# untitled.net
KiCad netlist of a schematic drawn in EAGLE
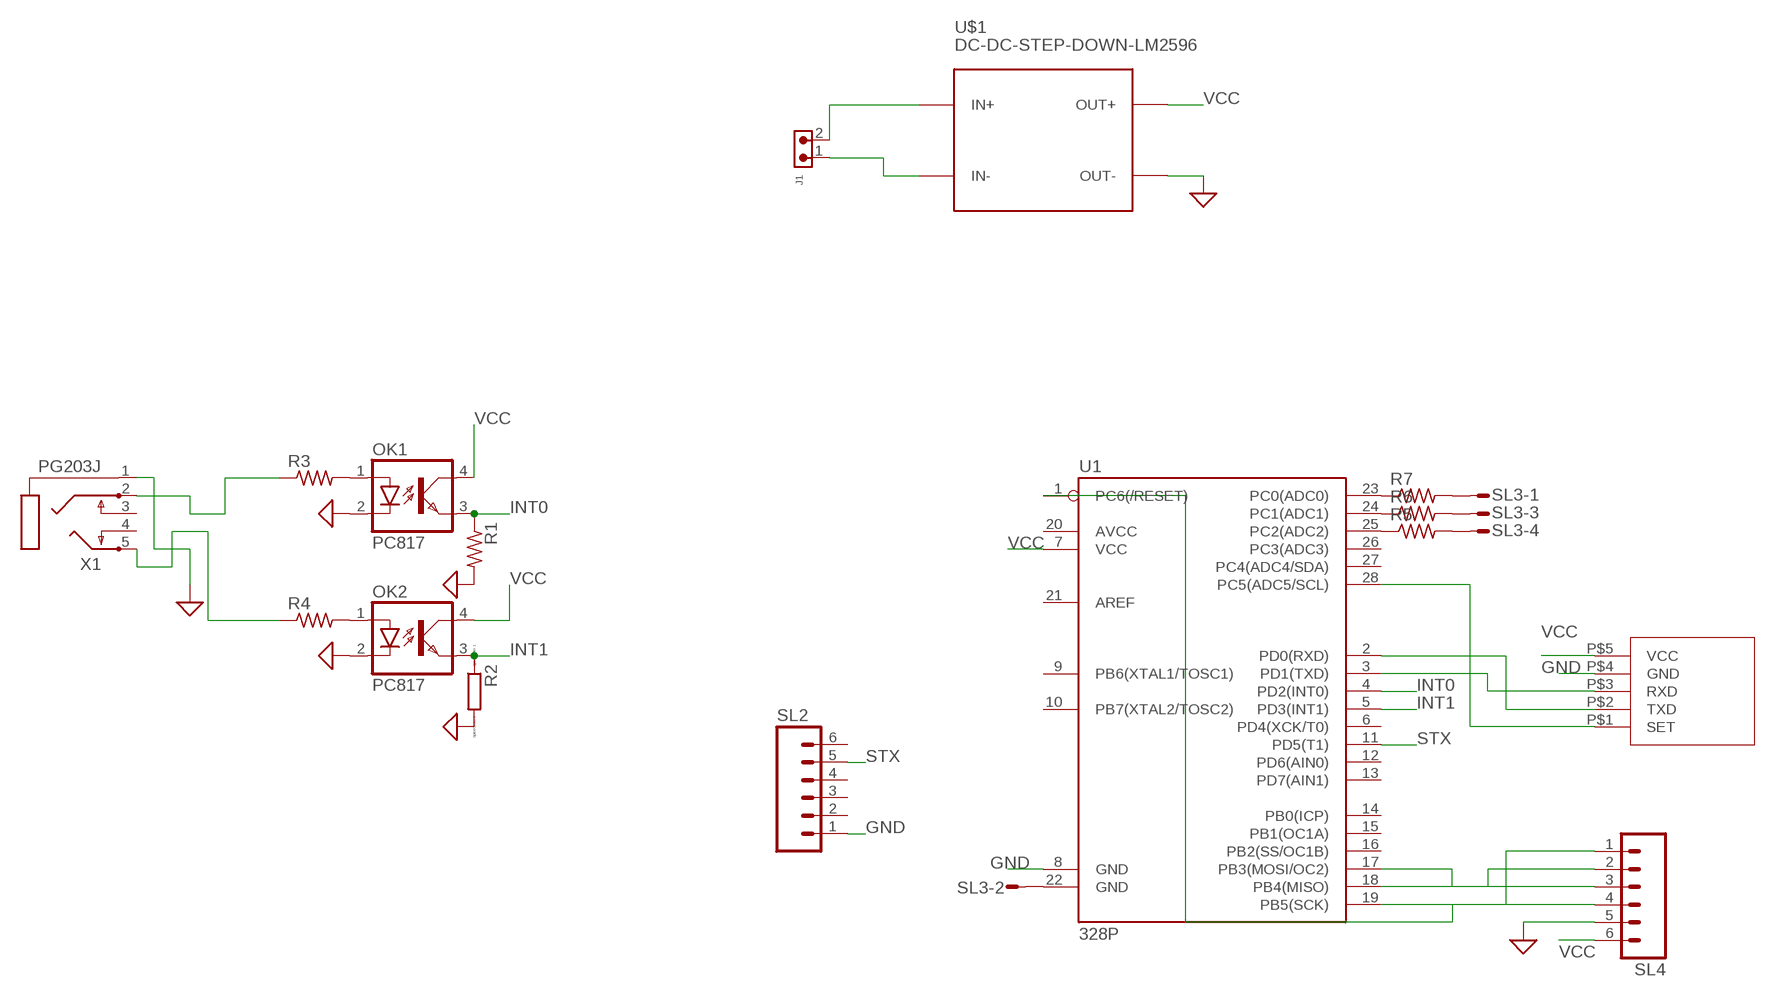
[diagram p0: schematic, sheet 1]

(export (version "E")
  (design (tool "Eeschema 10.0.6"))
  (components
    (comp (ref "J1")
      (value "691305530002")
      (footprint "eagle-import:691305530002")
      (libsource (lib "eagle-import") (part "691305530002"))
    )
    (comp (ref "OK1")
      (value "PC817")
      (footprint "eagle-import:DIL04")
      (fields (field (name "MPN") "PC817X4J000F"))
      (libsource (lib "eagle-import") (part "PC817"))
    )
    (comp (ref "OK2")
      (value "PC817")
      (footprint "eagle-import:DIL04")
      (fields (field (name "MPN") "PC817X4J000F"))
      (libsource (lib "eagle-import") (part "PC817"))
    )
    (comp (ref "R1")
      (value "R-US_0207/15")
      (footprint "eagle-import:0207_15")
      (libsource (lib "eagle-import") (part "R-US_0207/15"))
    )
    (comp (ref "R2")
      (value "R0207/10")
      (footprint "eagle-import:0207_10")
      (libsource (lib "eagle-import") (part "R0207/10"))
    )
    (comp (ref "R3")
      (value "R-US_0207/10")
      (footprint "eagle-import:0207_10")
      (libsource (lib "eagle-import") (part "R-US_0207/10"))
    )
    (comp (ref "R4")
      (value "R-US_0207/10")
      (footprint "eagle-import:0207_10")
      (libsource (lib "eagle-import") (part "R-US_0207/10"))
    )
    (comp (ref "R5")
      (value "R-US_0204/2V")
      (footprint "eagle-import:0204V")
      (libsource (lib "eagle-import") (part "R-US_0204/2V"))
    )
    (comp (ref "R6")
      (value "R-US_0204/2V")
      (footprint "eagle-import:0204V")
      (libsource (lib "eagle-import") (part "R-US_0204/2V"))
    )
    (comp (ref "R7")
      (value "R-US_0207/7")
      (footprint "eagle-import:0207_7")
      (libsource (lib "eagle-import") (part "R-US_0207/7"))
    )
    (comp (ref "SL2")
      (value "M06")
      (footprint "eagle-import:06P")
      (libsource (lib "eagle-import") (part "M06"))
    )
    (comp (ref "SL3")
      (value "M04S")
      (footprint "eagle-import:04P")
      (libsource (lib "eagle-import") (part "M04S"))
    )
    (comp (ref "SL4")
      (value "M06")
      (footprint "eagle-import:06P")
      (libsource (lib "eagle-import") (part "M06"))
    )
    (comp (ref "U$1")
      (value "DC-DC-STEP-DOWN-LM2596")
      (footprint "eagle-import:DC-DC-STEP-DOWN-LM2596")
      (libsource (lib "eagle-import") (part "DC-DC-STEP-DOWN-LM2596"))
    )
    (comp (ref "U$3")
      (value "HC12")
      (footprint "eagle-import:HC12")
      (libsource (lib "eagle-import") (part "HC12"))
    )
    (comp (ref "U1")
      (value "328P")
      (footprint "eagle-import:DIP28")
      (libsource (lib "eagle-import") (part "ATMEGA328P_PDIP"))
    )
    (comp (ref "X1")
      (value "PG203J")
      (footprint "eagle-import:PG203J")
      (libsource (lib "eagle-import") (part "PG203J"))
    )
  )
  (nets
    (net (code "1") (name "/INT0") (class "Default")
      (node (ref "OK1") (pin "3") (pinfunction "EMIT_3") (pintype "passive"))
      (node (ref "R1") (pin "1") (pinfunction "1_1") (pintype "passive"))
      (node (ref "U1") (pin "4") (pinfunction "PD2(INT0)_4") (pintype "bidirectional"))
    )
    (net (code "2") (name "/INT1") (class "Default")
      (node (ref "OK2") (pin "3") (pinfunction "EMIT_3") (pintype "passive"))
      (node (ref "R2") (pin "1") (pinfunction "1_1") (pintype "passive"))
      (node (ref "U1") (pin "5") (pinfunction "PD3(INT1)_5") (pintype "bidirectional"))
    )
    (net (code "3") (name "/STX") (class "Default")
      (node (ref "SL2") (pin "5") (pinfunction "5_5") (pintype "passive"))
      (node (ref "U1") (pin "11") (pinfunction "PD5(T1)_11") (pintype "bidirectional"))
    )
    (net (code "4") (name "/VCC") (class "Default")
      (node (ref "OK1") (pin "4") (pinfunction "COL_4") (pintype "passive"))
      (node (ref "OK2") (pin "4") (pinfunction "COL_4") (pintype "passive"))
      (node (ref "SL4") (pin "6") (pinfunction "6_6") (pintype "passive"))
      (node (ref "U$1") (pin "OUT+") (pinfunction "OUT+_OUT+") (pintype "bidirectional"))
      (node (ref "U$3") (pin "P$5") (pinfunction "VCC_P$5") (pintype "bidirectional"))
      (node (ref "U1") (pin "7") (pinfunction "VCC_7") (pintype "bidirectional"))
    )
    (net (code "5") (name "Net-(J1-Pad1)") (class "Default")
      (node (ref "J1") (pin "1") (pinfunction "1_1") (pintype "passive"))
      (node (ref "U$1") (pin "IN-") (pinfunction "IN-_IN-") (pintype "bidirectional"))
    )
    (net (code "6") (name "Net-(J1-Pad2)") (class "Default")
      (node (ref "J1") (pin "2") (pinfunction "2_2") (pintype "passive"))
      (node (ref "U$1") (pin "IN+") (pinfunction "IN+_IN+") (pintype "bidirectional"))
    )
    (net (code "7") (name "Net-(OK1-A)") (class "Default")
      (node (ref "OK1") (pin "1") (pinfunction "A_1") (pintype "passive"))
      (node (ref "R3") (pin "2") (pinfunction "2_2") (pintype "passive"))
    )
    (net (code "8") (name "Net-(OK2-A)") (class "Default")
      (node (ref "OK2") (pin "1") (pinfunction "A_1") (pintype "passive"))
      (node (ref "R4") (pin "2") (pinfunction "2_2") (pintype "passive"))
    )
    (net (code "9") (name "Net-(R3-Pad1)") (class "Default")
      (node (ref "R3") (pin "1") (pinfunction "1_1") (pintype "passive"))
      (node (ref "X1") (pin "2") (pinfunction "2_2") (pintype "passive"))
    )
    (net (code "10") (name "Net-(R4-Pad1)") (class "Default")
      (node (ref "R4") (pin "1") (pinfunction "1_1") (pintype "passive"))
      (node (ref "X1") (pin "5") (pinfunction "5_5") (pintype "passive"))
    )
    (net (code "11") (name "Net-(SL3A-S)") (class "Default")
      (node (ref "R7") (pin "2") (pinfunction "2_2") (pintype "passive"))
      (node (ref "SL3") (pin "1") (pinfunction "S_1") (pintype "passive"))
    )
    (net (code "12") (name "Net-(SL3B-S)") (class "Default")
      (node (ref "SL3") (pin "2") (pinfunction "S_2") (pintype "passive"))
      (node (ref "U1") (pin "22") (pinfunction "GND_22") (pintype "bidirectional"))
    )
    (net (code "13") (name "Net-(SL3C-S)") (class "Default")
      (node (ref "R6") (pin "2") (pinfunction "2_2") (pintype "passive"))
      (node (ref "SL3") (pin "3") (pinfunction "S_3") (pintype "passive"))
    )
    (net (code "14") (name "Net-(SL3D-S)") (class "Default")
      (node (ref "R5") (pin "2") (pinfunction "2_2") (pintype "passive"))
      (node (ref "SL3") (pin "4") (pinfunction "S_4") (pintype "passive"))
    )
    (net (code "15") (name "Net-(U$3-RXD)") (class "Default")
      (node (ref "U$3") (pin "P$3") (pinfunction "RXD_P$3") (pintype "bidirectional"))
      (node (ref "U1") (pin "3") (pinfunction "PD1(TXD)_3") (pintype "bidirectional"))
    )
    (net (code "16") (name "Net-(U$3-SET)") (class "Default")
      (node (ref "U$3") (pin "P$1") (pinfunction "SET_P$1") (pintype "bidirectional"))
      (node (ref "U1") (pin "28") (pinfunction "PC5(ADC5/SCL)_28") (pintype "bidirectional"))
    )
    (net (code "17") (name "Net-(U$3-TXD)") (class "Default")
      (node (ref "U$3") (pin "P$2") (pinfunction "TXD_P$2") (pintype "bidirectional"))
      (node (ref "U1") (pin "2") (pinfunction "PD0(RXD)_2") (pintype "bidirectional"))
    )
    (net (code "18") (name "Net-(U1-PB3(MOSI{slash}OC2))") (class "Default")
      (node (ref "SL4") (pin "3") (pinfunction "3_3") (pintype "passive"))
      (node (ref "U1") (pin "17") (pinfunction "PB3(MOSI/OC2)_17") (pintype "bidirectional"))
    )
    (net (code "19") (name "Net-(U1-PB4(MISO))") (class "Default")
      (node (ref "SL4") (pin "2") (pinfunction "2_2") (pintype "passive"))
      (node (ref "U1") (pin "18") (pinfunction "PB4(MISO)_18") (pintype "bidirectional"))
    )
    (net (code "20") (name "Net-(U1-PB5(SCK))") (class "Default")
      (node (ref "SL4") (pin "1") (pinfunction "1_1") (pintype "passive"))
      (node (ref "U1") (pin "19") (pinfunction "PB5(SCK)_19") (pintype "bidirectional"))
    )
    (net (code "21") (name "Net-(U1-PC0(ADC0))") (class "Default")
      (node (ref "R7") (pin "1") (pinfunction "1_1") (pintype "passive"))
      (node (ref "U1") (pin "23") (pinfunction "PC0(ADC0)_23") (pintype "bidirectional"))
    )
    (net (code "22") (name "Net-(U1-PC1(ADC1))") (class "Default")
      (node (ref "R6") (pin "1") (pinfunction "1_1") (pintype "passive"))
      (node (ref "U1") (pin "24") (pinfunction "PC1(ADC1)_24") (pintype "bidirectional"))
    )
    (net (code "23") (name "Net-(U1-PC2(ADC2))") (class "Default")
      (node (ref "R5") (pin "1") (pinfunction "1_1") (pintype "passive"))
      (node (ref "U1") (pin "25") (pinfunction "PC2(ADC2)_25") (pintype "bidirectional"))
    )
    (net (code "24") (name "Net-(U1-PC6({slash}RESET))") (class "Default")
      (node (ref "SL4") (pin "4") (pinfunction "4_4") (pintype "passive"))
      (node (ref "U1") (pin "1") (pinfunction "PC6(/RESET)_1") (pintype "bidirectional"))
    )
    (net (code "25") (name "SUP") (class "Default")
      (node (ref "OK1") (pin "2") (pinfunction "C_2") (pintype "passive"))
      (node (ref "OK2") (pin "2") (pinfunction "C_2") (pintype "passive"))
      (node (ref "R1") (pin "2") (pinfunction "2_2") (pintype "passive"))
      (node (ref "R2") (pin "2") (pinfunction "2_2") (pintype "passive"))
      (node (ref "SL2") (pin "1") (pinfunction "1_1") (pintype "passive"))
      (node (ref "SL4") (pin "5") (pinfunction "5_5") (pintype "passive"))
      (node (ref "U$1") (pin "OUT-") (pinfunction "OUT-_OUT-") (pintype "bidirectional"))
      (node (ref "U$3") (pin "P$4") (pinfunction "GND_P$4") (pintype "bidirectional"))
      (node (ref "U1") (pin "8") (pinfunction "GND_8") (pintype "bidirectional"))
      (node (ref "X1") (pin "1") (pinfunction "1_1") (pintype "passive"))
    )
    (net (code "26") (name "unconnected-(SL2-Pad2)") (class "Default")
      (node (ref "SL2") (pin "2") (pinfunction "2_2") (pintype "passive"))
    )
    (net (code "27") (name "unconnected-(SL2-Pad3)") (class "Default")
      (node (ref "SL2") (pin "3") (pinfunction "3_3") (pintype "passive"))
    )
    (net (code "28") (name "unconnected-(SL2-Pad4)") (class "Default")
      (node (ref "SL2") (pin "4") (pinfunction "4_4") (pintype "passive"))
    )
    (net (code "29") (name "unconnected-(SL2-Pad6)") (class "Default")
      (node (ref "SL2") (pin "6") (pinfunction "6_6") (pintype "passive"))
    )
    (net (code "30") (name "unconnected-(U1-AREF-Pad21)") (class "Default")
      (node (ref "U1") (pin "21") (pinfunction "AREF_21") (pintype "bidirectional"))
    )
    (net (code "31") (name "unconnected-(U1-AVCC-Pad20)") (class "Default")
      (node (ref "U1") (pin "20") (pinfunction "AVCC_20") (pintype "bidirectional"))
    )
    (net (code "32") (name "unconnected-(U1-PB0(ICP)-Pad14)") (class "Default")
      (node (ref "U1") (pin "14") (pinfunction "PB0(ICP)_14") (pintype "bidirectional"))
    )
    (net (code "33") (name "unconnected-(U1-PB1(OC1A)-Pad15)") (class "Default")
      (node (ref "U1") (pin "15") (pinfunction "PB1(OC1A)_15") (pintype "bidirectional"))
    )
    (net (code "34") (name "unconnected-(U1-PB2(SS{slash}OC1B)-Pad16)") (class "Default")
      (node (ref "U1") (pin "16") (pinfunction "PB2(SS/OC1B)_16") (pintype "bidirectional"))
    )
    (net (code "35") (name "unconnected-(U1-PB6(XTAL1{slash}TOSC1)-Pad9)") (class "Default")
      (node (ref "U1") (pin "9") (pinfunction "PB6(XTAL1/TOSC1)_9") (pintype "bidirectional"))
    )
    (net (code "36") (name "unconnected-(U1-PB7(XTAL2{slash}TOSC2)-Pad10)") (class "Default")
      (node (ref "U1") (pin "10") (pinfunction "PB7(XTAL2/TOSC2)_10") (pintype "bidirectional"))
    )
    (net (code "37") (name "unconnected-(U1-PC3(ADC3)-Pad26)") (class "Default")
      (node (ref "U1") (pin "26") (pinfunction "PC3(ADC3)_26") (pintype "bidirectional"))
    )
    (net (code "38") (name "unconnected-(U1-PC4(ADC4{slash}SDA)-Pad27)") (class "Default")
      (node (ref "U1") (pin "27") (pinfunction "PC4(ADC4/SDA)_27") (pintype "bidirectional"))
    )
    (net (code "39") (name "unconnected-(U1-PD4(XCK{slash}T0)-Pad6)") (class "Default")
      (node (ref "U1") (pin "6") (pinfunction "PD4(XCK/T0)_6") (pintype "bidirectional"))
    )
    (net (code "40") (name "unconnected-(U1-PD6(AIN0)-Pad12)") (class "Default")
      (node (ref "U1") (pin "12") (pinfunction "PD6(AIN0)_12") (pintype "bidirectional"))
    )
    (net (code "41") (name "unconnected-(U1-PD7(AIN1)-Pad13)") (class "Default")
      (node (ref "U1") (pin "13") (pinfunction "PD7(AIN1)_13") (pintype "bidirectional"))
    )
    (net (code "42") (name "unconnected-(X1-Pad3)") (class "Default")
      (node (ref "X1") (pin "3") (pinfunction "3_3") (pintype "passive"))
    )
    (net (code "43") (name "unconnected-(X1-Pad4)") (class "Default")
      (node (ref "X1") (pin "4") (pinfunction "4_4") (pintype "passive"))
    )
  )
)
